# Charge.net
KiCad netlist of a schematic drawn in Altium Designer
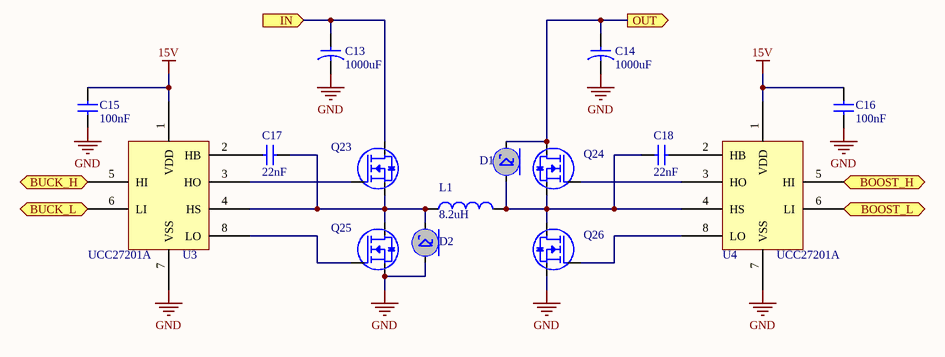
[diagram p0: Charge.SchDoc]

(export (version "E")
  (design (tool "Eeschema 10.0.6"))
  (components
    (comp (ref "C13")
      (value "1000uF")
      (footprint "CAP1000uF")
      (fields (field (name "Comment") "CapPol"))
      (libsource (lib "SubjuGator8") (part "CapPol"))
    )
    (comp (ref "C14")
      (value "1000uF")
      (footprint "CAP1000uF")
      (fields (field (name "Comment") "CapPol"))
      (libsource (lib "SubjuGator8") (part "CapPol"))
    )
    (comp (ref "C15")
      (value "100nF")
      (footprint "CAPC0603")
      (fields (field (name "Comment") "Cap"))
      (libsource (lib "SubjuGator8") (part "Cap"))
    )
    (comp (ref "C16")
      (value "100nF")
      (footprint "CAPC0603")
      (fields (field (name "Comment") "Cap"))
      (libsource (lib "SubjuGator8") (part "Cap"))
    )
    (comp (ref "C17")
      (value "22nF")
      (footprint "CAPC0603")
      (fields (field (name "Comment") "Cap"))
      (libsource (lib "SubjuGator8") (part "Cap"))
    )
    (comp (ref "C18")
      (value "22nF")
      (footprint "CAPC0603")
      (fields (field (name "Comment") "Cap"))
      (libsource (lib "SubjuGator8") (part "Cap"))
    )
    (comp (ref "D1")
      (value "DFLS160")
      (footprint "POWERDI123")
      (description "1.0A Surface Mount Schottky Barrier Rectifier")
      (libsource (lib "SubjuGator8") (part "DFLS160"))
    )
    (comp (ref "D2")
      (value "DFLS160")
      (footprint "POWERDI123")
      (description "1.0A Surface Mount Schottky Barrier Rectifier")
      (libsource (lib "SubjuGator8") (part "DFLS160"))
    )
    (comp (ref "L1")
      (value "Inductor")
      (footprint "IHLP-6767")
      (fields (field (name "INDUCTANCE") "8.2uH"))
      (libsource (lib "SubjuGator8") (part "Inductor"))
    )
    (comp (ref "Q23")
      (value "IRFB3306PbF")
      (footprint "TO-220AB Heatsink")
      (description "HEXFET Power MOSFET")
      (libsource (lib "") (part "IRFx3306PbF_1"))
    )
    (comp (ref "Q24")
      (value "IRFB3306PbF")
      (footprint "TO-220AB Heatsink")
      (description "HEXFET Power MOSFET")
      (libsource (lib "SubjuGator8") (part "IRFx3306PbF"))
    )
    (comp (ref "Q25")
      (value "IRFB3306PbF")
      (footprint "TO-220AB Heatsink")
      (description "HEXFET Power MOSFET")
      (libsource (lib "") (part "IRFx3306PbF_1"))
    )
    (comp (ref "Q26")
      (value "IRFB3306PbF")
      (footprint "TO-220AB Heatsink")
      (description "HEXFET Power MOSFET")
      (libsource (lib "SubjuGator8") (part "IRFx3306PbF"))
    )
    (comp (ref "U3")
      (value "UCC27201A")
      (footprint "UCC27201A")
      (description "IC DVR HIGH/LOW SIDE 3A 8SOPWR")
      (libsource (lib "SubjuGator8") (part "UCC27201A"))
    )
    (comp (ref "U4")
      (value "UCC27201A")
      (footprint "UCC27201A")
      (description "IC DVR HIGH/LOW SIDE 3A 8SOPWR")
      (libsource (lib "") (part "UCC27201A_1"))
    )
  )
  (nets
    (net (code "1") (name "/BOOST_H") (class "Default")
      (node (ref "U4") (pin "5") (pinfunction "HI_5") (pintype "passive"))
    )
    (net (code "2") (name "/BOOST_L") (class "Default")
      (node (ref "U4") (pin "6") (pinfunction "LI_6") (pintype "passive"))
    )
    (net (code "3") (name "/BUCK_H") (class "Default")
      (node (ref "U3") (pin "5") (pinfunction "HI_5") (pintype "passive"))
    )
    (net (code "4") (name "/BUCK_L") (class "Default")
      (node (ref "U3") (pin "6") (pinfunction "LI_6") (pintype "passive"))
    )
    (net (code "5") (name "/IN") (class "Default")
      (node (ref "C13") (pin "1") (pinfunction "A_1") (pintype "passive"))
      (node (ref "Q23") (pin "D") (pinfunction "D_D") (pintype "passive"))
    )
    (net (code "6") (name "/OUT") (class "Default")
      (node (ref "C14") (pin "1") (pinfunction "A_1") (pintype "passive"))
      (node (ref "D1") (pin "C") (pinfunction "C_C") (pintype "passive"))
      (node (ref "Q24") (pin "D") (pinfunction "D_D") (pintype "passive"))
    )
    (net (code "7") (name "15V") (class "Default")
      (node (ref "C15") (pin "1") (pinfunction "A_1") (pintype "passive"))
      (node (ref "C16") (pin "1") (pinfunction "A_1") (pintype "passive"))
      (node (ref "U3") (pin "1") (pinfunction "VDD_1") (pintype "passive"))
      (node (ref "U4") (pin "1") (pinfunction "VDD_1") (pintype "passive"))
    )
    (net (code "8") (name "GND") (class "Default")
      (node (ref "C13") (pin "2") (pinfunction "B_2") (pintype "passive"))
      (node (ref "C14") (pin "2") (pinfunction "B_2") (pintype "passive"))
      (node (ref "C15") (pin "2") (pinfunction "B_2") (pintype "passive"))
      (node (ref "C16") (pin "2") (pinfunction "B_2") (pintype "passive"))
      (node (ref "D2") (pin "A") (pinfunction "A_A") (pintype "passive"))
      (node (ref "Q25") (pin "S") (pinfunction "S_S") (pintype "passive"))
      (node (ref "Q26") (pin "S") (pinfunction "S_S") (pintype "passive"))
      (node (ref "U3") (pin "7") (pinfunction "VSS_7") (pintype "passive"))
      (node (ref "U4") (pin "7") (pinfunction "VSS_7") (pintype "passive"))
    )
    (net (code "9") (name "Net-(C17-A)") (class "Default")
      (node (ref "C17") (pin "1") (pinfunction "A_1") (pintype "passive"))
      (node (ref "D2") (pin "C") (pinfunction "C_C") (pintype "passive"))
      (node (ref "L1") (pin "1") (pinfunction "A_1") (pintype "passive"))
      (node (ref "Q23") (pin "S") (pinfunction "S_S") (pintype "passive"))
      (node (ref "Q25") (pin "D") (pinfunction "D_D") (pintype "passive"))
      (node (ref "U3") (pin "4") (pinfunction "HS_4") (pintype "passive"))
    )
    (net (code "10") (name "Net-(C17-B)") (class "Default")
      (node (ref "C17") (pin "2") (pinfunction "B_2") (pintype "passive"))
      (node (ref "U3") (pin "2") (pinfunction "HB_2") (pintype "passive"))
    )
    (net (code "11") (name "Net-(C18-A)") (class "Default")
      (node (ref "C18") (pin "1") (pinfunction "A_1") (pintype "passive"))
      (node (ref "D1") (pin "A") (pinfunction "A_A") (pintype "passive"))
      (node (ref "L1") (pin "2") (pinfunction "B_2") (pintype "passive"))
      (node (ref "Q24") (pin "S") (pinfunction "S_S") (pintype "passive"))
      (node (ref "Q26") (pin "D") (pinfunction "D_D") (pintype "passive"))
      (node (ref "U4") (pin "4") (pinfunction "HS_4") (pintype "passive"))
    )
    (net (code "12") (name "Net-(C18-B)") (class "Default")
      (node (ref "C18") (pin "2") (pinfunction "B_2") (pintype "passive"))
      (node (ref "U4") (pin "2") (pinfunction "HB_2") (pintype "passive"))
    )
    (net (code "13") (name "Net-(U3-HO)") (class "Default")
      (node (ref "Q23") (pin "G") (pinfunction "G_G") (pintype "passive"))
      (node (ref "U3") (pin "3") (pinfunction "HO_3") (pintype "passive"))
    )
    (net (code "14") (name "Net-(U3-LO)") (class "Default")
      (node (ref "Q25") (pin "G") (pinfunction "G_G") (pintype "passive"))
      (node (ref "U3") (pin "8") (pinfunction "LO_8") (pintype "passive"))
    )
    (net (code "15") (name "Net-(U4-HO)") (class "Default")
      (node (ref "Q24") (pin "G") (pinfunction "G_G") (pintype "passive"))
      (node (ref "U4") (pin "3") (pinfunction "HO_3") (pintype "passive"))
    )
    (net (code "16") (name "Net-(U4-LO)") (class "Default")
      (node (ref "Q26") (pin "G") (pinfunction "G_G") (pintype "passive"))
      (node (ref "U4") (pin "8") (pinfunction "LO_8") (pintype "passive"))
    )
  )
)
